# ST_LINK_V2-1.net
KiCad netlist of a schematic drawn in Altium Designer
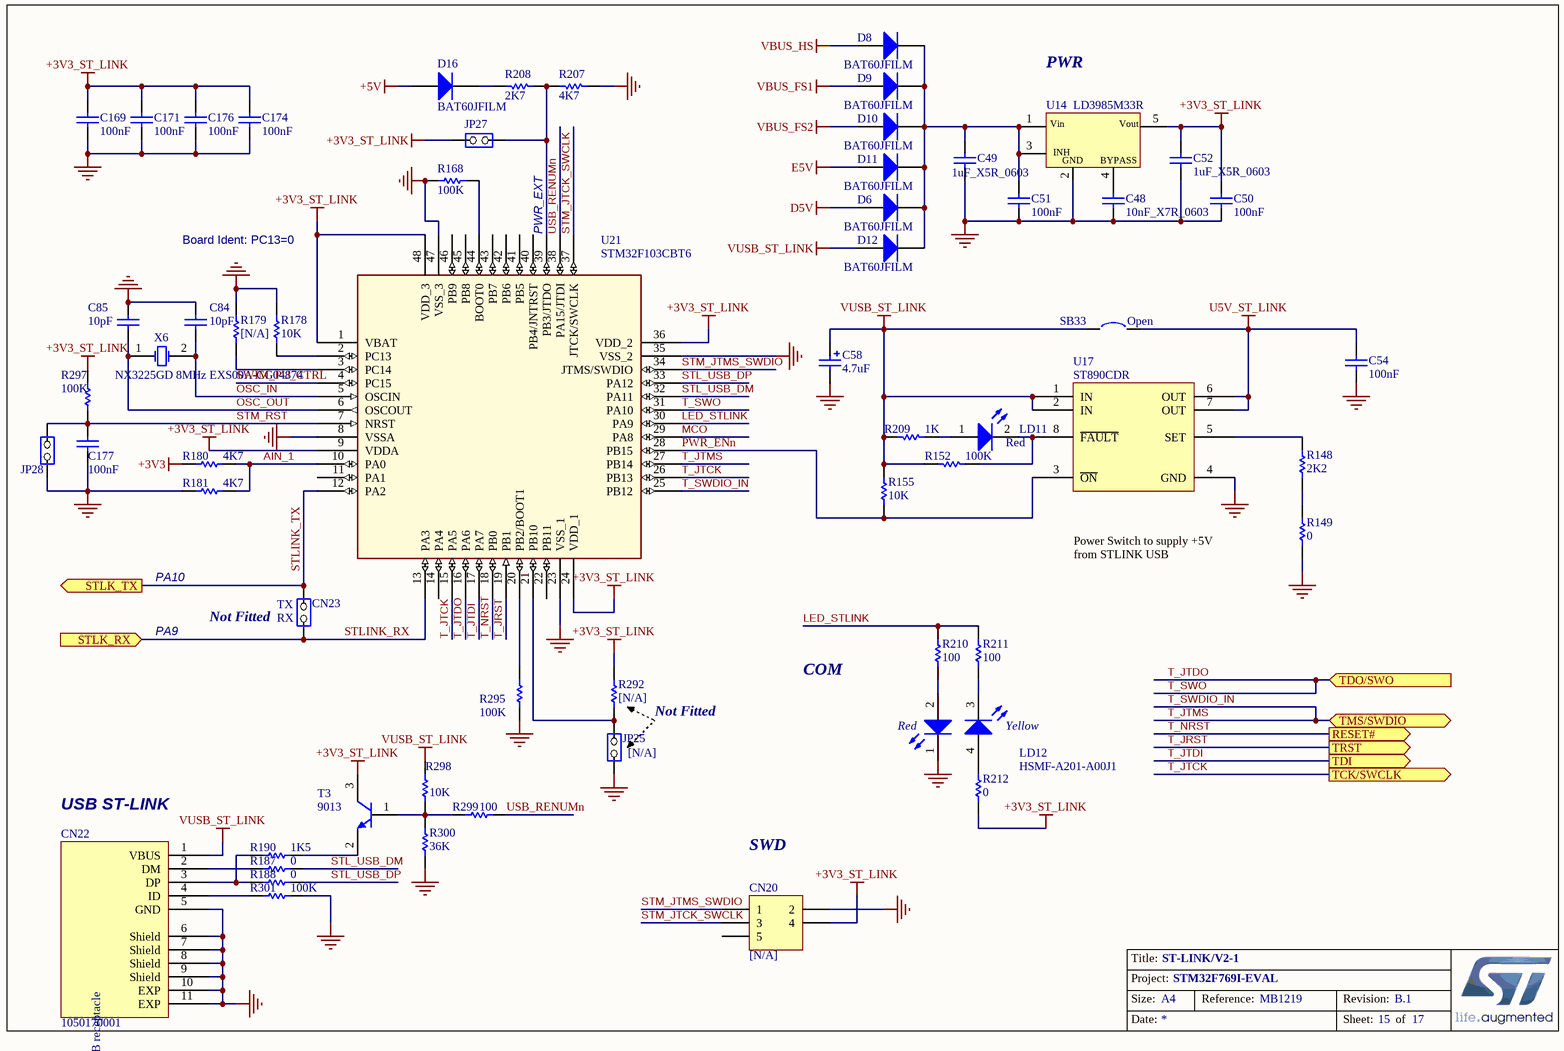
[diagram p0: ST_LINK_V2-1.SCHDOC]

(export (version "E")
  (design (tool "Eeschema 10.0.6"))
  (components
    (comp (ref "C48")
      (value "10nF_X7R_0603")
      (footprint "0603C")
      (description "0603  X7R 10NF")
      (fields (field (name "TOLERANCE") "10%"))
      (libsource (lib "MB963_1") (part "CAP SMD 0603  X7R 10000PF 50V 10%"))
    )
    (comp (ref "C49")
      (value "1uF_X5R_0603")
      (footprint "0603C")
      (description "0603  X5R 1µF")
      (fields (field (name "TOLERANCE") "10%"))
      (libsource (lib "MB963_1") (part "CAP SMD 0603  X5R 1µF 25V 10%"))
    )
    (comp (ref "C50")
      (value "100nF")
      (footprint "0603C")
      (description "Capacitor 0402 / 0603 / 0805")
      (libsource (lib "MCD_TOOLS") (part "Capacitor_ST"))
    )
    (comp (ref "C51")
      (value "100nF")
      (footprint "0603C")
      (description "Capacitor 0402 / 0603 / 0805")
      (libsource (lib "MCD_TOOLS") (part "Capacitor_ST"))
    )
    (comp (ref "C52")
      (value "1uF_X5R_0603")
      (footprint "0603C")
      (description "0603  X5R 1µF")
      (fields (field (name "TOLERANCE") "10%"))
      (libsource (lib "MB963_1") (part "CAP SMD 0603  X5R 1µF 25V 10%"))
    )
    (comp (ref "C54")
      (value "100nF")
      (footprint "0603C")
      (description "Capacitor 0402 / 0603 / 0805")
      (libsource (lib "MCD_TOOLS") (part "Capacitor_ST"))
    )
    (comp (ref "C58")
      (value "4.7uF")
      (footprint "TAN-A")
      (description "Polarized Capacitor (Radial)")
      (fields (field (name "PUBLISHER") "Altium Limited"))
      (libsource (lib "*") (part "Cap Pol1"))
    )
    (comp (ref "C84")
      (value "10pF")
      (footprint "0603C")
      (description "Capacitor 0402 / 0603 / 0805")
      (libsource (lib "MCD_TOOLS") (part "Capacitor_ST"))
    )
    (comp (ref "C85")
      (value "10pF")
      (footprint "0603C")
      (description "Capacitor 0402 / 0603 / 0805")
      (libsource (lib "MCD_TOOLS") (part "Capacitor_ST"))
    )
    (comp (ref "C169")
      (value "100nF")
      (footprint "0603C")
      (description "Capacitor 0402 / 0603 / 0805")
      (libsource (lib "MCD_TOOLS") (part "Capacitor_ST"))
    )
    (comp (ref "C171")
      (value "100nF")
      (footprint "0603C")
      (description "Capacitor 0402 / 0603 / 0805")
      (libsource (lib "MCD_TOOLS") (part "Capacitor_ST"))
    )
    (comp (ref "C174")
      (value "100nF")
      (footprint "0603C")
      (description "Capacitor 0402 / 0603 / 0805")
      (libsource (lib "MCD_TOOLS") (part "Capacitor_ST"))
    )
    (comp (ref "C176")
      (value "100nF")
      (footprint "0603C")
      (description "Capacitor 0402 / 0603 / 0805")
      (libsource (lib "MCD_TOOLS") (part "Capacitor_ST"))
    )
    (comp (ref "C177")
      (value "100nF")
      (footprint "0603C")
      (description "Capacitor 0402 / 0603 / 0805")
      (libsource (lib "MCD_TOOLS") (part "Capacitor_ST"))
    )
    (comp (ref "CN20")
      (value "[N/A]")
      (footprint "HDR_2X3-1_2R54-6")
      (description "Header, 3-Pin, Dual row")
      (fields (field (name "PUBLISHER") "Altium Limited"))
      (libsource (lib "Miscellaneous Connectors") (part "Header 3X2"))
    )
    (comp (ref "CN22")
      (value "1050170001")
      (footprint "Molex_1050170001")
      (libsource (lib "MB1219") (part "1050170001"))
    )
    (comp (ref "CN23") (value "~") (footprint "SIP2") (libsource (lib "MCD_TOOLS") (part "JP2")))
    (comp (ref "D6")
      (value "BAT60JFILM")
      (footprint "SOD-323")
      (libsource (lib "MCD_TOOLS") (part "BAT60JFILM"))
    )
    (comp (ref "D8")
      (value "BAT60JFILM")
      (footprint "SOD-323")
      (libsource (lib "MCD_TOOLS") (part "BAT60JFILM"))
    )
    (comp (ref "D9")
      (value "BAT60JFILM")
      (footprint "SOD-323")
      (libsource (lib "MCD_TOOLS") (part "BAT60JFILM"))
    )
    (comp (ref "D10")
      (value "BAT60JFILM")
      (footprint "SOD-323")
      (libsource (lib "MCD_TOOLS") (part "BAT60JFILM"))
    )
    (comp (ref "D11")
      (value "BAT60JFILM")
      (footprint "SOD-323")
      (libsource (lib "MCD_TOOLS") (part "BAT60JFILM"))
    )
    (comp (ref "D12")
      (value "BAT60JFILM")
      (footprint "SOD-323")
      (libsource (lib "MCD_TOOLS") (part "BAT60JFILM"))
    )
    (comp (ref "D16")
      (value "BAT60JFILM")
      (footprint "SOD-323")
      (description "Default Diode")
      (fields (field (name "PUBLISHER") "Altium Limited"))
      (libsource (lib "MB1144_1") (part "Diode"))
    )
    (comp (ref "JP25") (value "[N/A]") (footprint "SIP2") (libsource (lib "*") (part "JP2")))
    (comp (ref "JP27") (value "~") (footprint "SIP2") (libsource (lib "*") (part "JP2")))
    (comp (ref "JP28") (value "~") (footprint "SIP2") (libsource (lib "*") (part "JP2")))
    (comp (ref "LD11")
      (value "Red")
      (footprint "0603D")
      (description "Typical RED, GREEN, YELLOW, AMBER GaAs LED")
      (fields (field (name "PUBLISHER") "Altium Limited"))
      (libsource (lib "Miscellaneous Devices") (part "LED2"))
    )
    (comp (ref "LD12")
      (value "HSMF-A201-A00J1")
      (footprint "LED2_3528")
      (libsource (lib "MB819") (part "HSMF-A201-A00J1"))
    )
    (comp (ref "R148")
      (value "2K2")
      (footprint "0402R")
      (description "Resistor 0402 or 0603 or 0805")
      (libsource (lib "MCD_TOOLS") (part "Resistor_ST"))
    )
    (comp (ref "R149")
      (value "0")
      (footprint "0603R")
      (description "Resistor")
      (fields (field (name "PUBLISHER") "Altium Limited"))
      (libsource (lib "Miscellaneous Devices") (part "Res1"))
    )
    (comp (ref "R152")
      (value "100K")
      (footprint "0603R")
      (description "Resistor")
      (fields (field (name "PUBLISHER") "Altium Limited"))
      (libsource (lib "*") (part "Res1"))
    )
    (comp (ref "R155")
      (value "10K")
      (footprint "0402R")
      (description "Resistor 0402 or 0603 or 0805")
      (libsource (lib "MCD_TOOLS") (part "Resistor_ST"))
    )
    (comp (ref "R168")
      (value "100K")
      (footprint "0603R")
      (description "Resistor 0402 or 0603 or 0805")
      (libsource (lib "") (part "Res1_1"))
    )
    (comp (ref "R178")
      (value "10K")
      (footprint "0603R")
      (description "Resistor 0402 or 0603 or 0805")
      (libsource (lib "") (part "Res1_1"))
    )
    (comp (ref "R179")
      (value "[N/A]")
      (footprint "0603R")
      (description "Resistor 0402 or 0603 or 0805")
      (libsource (lib "") (part "Res1_1"))
    )
    (comp (ref "R180")
      (value "4K7")
      (footprint "0603R")
      (description "Resistor 0402 or 0603 or 0805")
      (libsource (lib "") (part "Res1_1"))
    )
    (comp (ref "R181")
      (value "4K7")
      (footprint "0603R")
      (description "Resistor 0402 or 0603 or 0805")
      (libsource (lib "") (part "Res1_1"))
    )
    (comp (ref "R187")
      (value "0")
      (footprint "0603R")
      (description "Resistor 0402 or 0603 or 0805")
      (libsource (lib "") (part "Res1_1"))
    )
    (comp (ref "R188")
      (value "0")
      (footprint "0603R")
      (description "Resistor 0402 or 0603 or 0805")
      (libsource (lib "") (part "Res1_1"))
    )
    (comp (ref "R190")
      (value "1K5")
      (footprint "0603R")
      (description "Resistor 0402 or 0603 or 0805")
      (libsource (lib "") (part "Res1_1"))
    )
    (comp (ref "R207")
      (value "4K7")
      (footprint "0603R")
      (description "Resistor")
      (fields (field (name "PUBLISHER") "Altium Limited"))
      (libsource (lib "") (part "Res1_2"))
    )
    (comp (ref "R208")
      (value "2K7")
      (footprint "0603R")
      (description "Resistor")
      (fields (field (name "PUBLISHER") "Altium Limited"))
      (libsource (lib "") (part "Res1_2"))
    )
    (comp (ref "R209")
      (value "1K")
      (footprint "0603R")
      (description "Resistor")
      (fields (field (name "PUBLISHER") "Altium Limited"))
      (libsource (lib "*") (part "Res1"))
    )
    (comp (ref "R210")
      (value "100")
      (footprint "0603R")
      (description "Resistor")
      (fields (field (name "PUBLISHER") "Altium Limited"))
      (libsource (lib "Miscellaneous Devices") (part "Res1"))
    )
    (comp (ref "R211")
      (value "100")
      (footprint "0603R")
      (description "Resistor")
      (fields (field (name "PUBLISHER") "Altium Limited"))
      (libsource (lib "Miscellaneous Devices") (part "Res1"))
    )
    (comp (ref "R212")
      (value "0")
      (footprint "0603R")
      (description "Resistor")
      (fields (field (name "PUBLISHER") "Altium Limited"))
      (libsource (lib "Miscellaneous Devices") (part "Res1"))
    )
    (comp (ref "R292")
      (value "[N/A]")
      (footprint "0603R")
      (description "Resistor")
      (fields (field (name "PUBLISHER") "Altium Limited"))
      (libsource (lib "Miscellaneous Devices") (part "Res1"))
    )
    (comp (ref "R295")
      (value "100K")
      (footprint "0603R")
      (description "Resistor 0402 or 0603 or 0805")
      (libsource (lib "") (part "Res1_1"))
    )
    (comp (ref "R297")
      (value "100K")
      (footprint "0603R")
      (description "Resistor 0402 or 0603 or 0805")
      (libsource (lib "") (part "Res1_1"))
    )
    (comp (ref "R298")
      (value "10K")
      (footprint "0603R")
      (description "Resistor")
      (fields (field (name "PUBLISHER") "Altium Limited"))
      (libsource (lib "Miscellaneous Devices") (part "Res1"))
    )
    (comp (ref "R299")
      (value "100")
      (footprint "0603R")
      (description "Resistor 0402 or 0603 or 0805")
      (libsource (lib "") (part "Res1_1"))
    )
    (comp (ref "R300")
      (value "36K")
      (footprint "0603R")
      (description "Resistor")
      (fields (field (name "PUBLISHER") "Altium Limited"))
      (libsource (lib "Miscellaneous Devices") (part "Res1"))
    )
    (comp (ref "R301")
      (value "100K")
      (footprint "0603R")
      (description "Resistor 0402 or 0603 or 0805")
      (libsource (lib "") (part "Res1_1"))
    )
    (comp (ref "SB33")
      (value "Open")
      (footprint "SB_0603")
      (description "Circuit Breaker")
      (fields (field (name "PUBLISHER") "Altium Limited"))
      (libsource (lib "MB1167") (part "Circuit Breaker"))
    )
    (comp (ref "T3")
      (value "9013")
      (footprint "SOT-23")
      (description "NPN Bipolar Transistor")
      (fields (field (name "PUBLISHER") "Altium Limited"))
      (libsource (lib "MB1167") (part "NPN"))
    )
    (comp (ref "U14")
      (value "LD3985M33R")
      (footprint "SOT23-5")
      (description "Ultra low drop-low noise BiCMOS voltage, regulators low ESR capacitors compatible")
      (libsource (lib "MCD_TOOLS") (part "LD3985M33R"))
    )
    (comp (ref "U17")
      (value "ST890CDR")
      (footprint "SOIC8_1R27_4R9X6")
      (libsource (lib "MB1219") (part "ST890CDR"))
    )
    (comp (ref "U21")
      (value "STM32F103CBT6")
      (footprint "LQFP48_0R5_9X9")
      (description "Medium-density performance line ARM-based 32-bit MCU with 64KB Flash")
      (libsource (lib "Nucleo_64") (part "STM32F103CBT6"))
    )
    (comp (ref "X6")
      (value "NX3225GD 8MHz EXS00A-CG04874")
      (footprint "XTAL_2SM_3R2X2R5_H1")
      (description "Crystal Oscillator")
      (fields (field (name "PUBLISHER") "Altium Limited"))
      (libsource (lib "MB963_1") (part "XTAL"))
    )
  )
  (nets
    (net (code "1") (name "+3V3") (class "Default")
      (node (ref "R180") (pin "1") (pinfunction "1_1") (pintype "passive"))
    )
    (net (code "2") (name "+3V3_ST_LINK") (class "Default")
      (node (ref "C169") (pin "2") (pinfunction "2_2") (pintype "passive"))
      (node (ref "C171") (pin "2") (pinfunction "2_2") (pintype "passive"))
      (node (ref "C174") (pin "2") (pinfunction "2_2") (pintype "passive"))
      (node (ref "C176") (pin "2") (pinfunction "2_2") (pintype "passive"))
      (node (ref "C50") (pin "2") (pinfunction "2_2") (pintype "passive"))
      (node (ref "C52") (pin "1") (pinfunction "1_1") (pintype "passive"))
      (node (ref "CN20") (pin "4") (pinfunction "4_4") (pintype "passive"))
      (node (ref "JP27") (pin "1") (pinfunction "COMMON_1") (pintype "passive"))
      (node (ref "R212") (pin "2") (pinfunction "2_2") (pintype "passive"))
      (node (ref "R292") (pin "1") (pinfunction "1_1") (pintype "passive"))
      (node (ref "R297") (pin "2") (pinfunction "2_2") (pintype "passive"))
      (node (ref "T3") (pin "3") (pinfunction "C_3") (pintype "passive"))
      (node (ref "U14") (pin "5") (pinfunction "Vout_5") (pintype "passive"))
      (node (ref "U21") (pin "1") (pinfunction "VBAT_1") (pintype "power_in"))
      (node (ref "U21") (pin "24") (pinfunction "VDD_1_24") (pintype "power_in"))
      (node (ref "U21") (pin "36") (pinfunction "VDD_2_36") (pintype "power_in"))
      (node (ref "U21") (pin "48") (pinfunction "VDD_3_48") (pintype "power_in"))
      (node (ref "U21") (pin "9") (pinfunction "VDDA_9") (pintype "power_in"))
    )
    (net (code "3") (name "+5V") (class "Default")
      (node (ref "D16") (pin "1") (pinfunction "A_1") (pintype "passive"))
    )
    (net (code "4") (name "/AIN_1") (class "Default")
      (node (ref "R180") (pin "2") (pinfunction "2_2") (pintype "passive"))
      (node (ref "R181") (pin "2") (pinfunction "2_2") (pintype "passive"))
      (node (ref "U21") (pin "10") (pinfunction "PA0_10") (pintype "bidirectional"))
    )
    (net (code "5") (name "/LED_STLINK") (class "Default")
      (node (ref "R210") (pin "1") (pinfunction "1_1") (pintype "passive"))
      (node (ref "R211") (pin "1") (pinfunction "1_1") (pintype "passive"))
      (node (ref "U21") (pin "30") (pinfunction "PA9_30") (pintype "bidirectional"))
    )
    (net (code "6") (name "/MCO") (class "Default")
      (node (ref "U21") (pin "29") (pinfunction "PA8_29") (pintype "bidirectional"))
    )
    (net (code "7") (name "/OSC_IN") (class "Default")
      (node (ref "C84") (pin "1") (pinfunction "1_1") (pintype "passive"))
      (node (ref "U21") (pin "5") (pinfunction "OSCIN_5") (pintype "input"))
      (node (ref "X6") (pin "2") (pinfunction "OSC2_2") (pintype "passive"))
    )
    (net (code "8") (name "/OSC_OUT") (class "Default")
      (node (ref "C85") (pin "1") (pinfunction "1_1") (pintype "passive"))
      (node (ref "U21") (pin "6") (pinfunction "OSCOUT_6") (pintype "output"))
      (node (ref "X6") (pin "1") (pinfunction "OSC1_1") (pintype "passive"))
    )
    (net (code "9") (name "/PWR_ENn") (class "Default")
      (node (ref "R155") (pin "2") (pinfunction "2_2") (pintype "passive"))
      (node (ref "U17") (pin "3") (pinfunction "~{ON}_3") (pintype "passive"))
      (node (ref "U21") (pin "28") (pinfunction "PB15_28") (pintype "bidirectional"))
    )
    (net (code "10") (name "/STLINK_RX") (class "Default")
      (node (ref "CN23") (pin "1") (pinfunction "COMMON_1") (pintype "passive"))
      (node (ref "U21") (pin "13") (pinfunction "PA3_13") (pintype "bidirectional"))
    )
    (net (code "11") (name "/STLINK_TX") (class "Default")
      (node (ref "CN23") (pin "2") (pinfunction "NO_2") (pintype "passive"))
      (node (ref "U21") (pin "12") (pinfunction "PA2_12") (pintype "bidirectional"))
    )
    (net (code "12") (name "/STL_USB_DM") (class "Default")
      (node (ref "R187") (pin "2") (pinfunction "2_2") (pintype "passive"))
      (node (ref "U21") (pin "32") (pinfunction "PA11_32") (pintype "bidirectional"))
    )
    (net (code "13") (name "/STL_USB_DP") (class "Default")
      (node (ref "R188") (pin "2") (pinfunction "2_2") (pintype "passive"))
      (node (ref "U21") (pin "33") (pinfunction "PA12_33") (pintype "bidirectional"))
    )
    (net (code "14") (name "/STM_JTCK_SWCLK") (class "Default")
      (node (ref "CN20") (pin "3") (pinfunction "3_3") (pintype "passive"))
      (node (ref "U21") (pin "37") (pinfunction "JTCK/SWCLK_37") (pintype "bidirectional"))
    )
    (net (code "15") (name "/STM_JTMS_SWDIO") (class "Default")
      (node (ref "CN20") (pin "1") (pinfunction "1_1") (pintype "passive"))
      (node (ref "U21") (pin "34") (pinfunction "JTMS/SWDIO_34") (pintype "bidirectional"))
    )
    (net (code "16") (name "/STM_RST") (class "Default")
      (node (ref "C177") (pin "2") (pinfunction "2_2") (pintype "passive"))
      (node (ref "JP28") (pin "2") (pinfunction "NO_2") (pintype "passive"))
      (node (ref "R297") (pin "1") (pinfunction "1_1") (pintype "passive"))
      (node (ref "U21") (pin "7") (pinfunction "NRST_7") (pintype "input"))
    )
    (net (code "17") (name "/SWIM_PU_CTRL") (class "Default")
      (node (ref "U21") (pin "4") (pinfunction "PC15_4") (pintype "bidirectional"))
    )
    (net (code "18") (name "/T_JRST") (class "Default")
      (node (ref "U21") (pin "19") (pinfunction "PB1_19") (pintype "input"))
    )
    (net (code "19") (name "/T_JTCK") (class "Default")
      (node (ref "U21") (pin "15") (pinfunction "PA5_15") (pintype "bidirectional"))
      (node (ref "U21") (pin "26") (pinfunction "PB13_26") (pintype "bidirectional"))
    )
    (net (code "20") (name "/T_JTDI") (class "Default")
      (node (ref "U21") (pin "17") (pinfunction "PA7_17") (pintype "bidirectional"))
    )
    (net (code "21") (name "/T_JTDO") (class "Default")
      (node (ref "U21") (pin "16") (pinfunction "PA6_16") (pintype "bidirectional"))
      (node (ref "U21") (pin "31") (pinfunction "PA10_31") (pintype "bidirectional"))
    )
    (net (code "22") (name "/T_JTMS") (class "Default")
      (node (ref "U21") (pin "25") (pinfunction "PB12_25") (pintype "bidirectional"))
      (node (ref "U21") (pin "27") (pinfunction "PB14_27") (pintype "bidirectional"))
    )
    (net (code "23") (name "/T_NRST") (class "Default")
      (node (ref "U21") (pin "18") (pinfunction "PB0_18") (pintype "bidirectional"))
    )
    (net (code "24") (name "/USB_RENUMn") (class "Default")
      (node (ref "R299") (pin "2") (pinfunction "2_2") (pintype "passive"))
      (node (ref "U21") (pin "38") (pinfunction "PA15/JTDI_38") (pintype "bidirectional"))
    )
    (net (code "25") (name "D5V") (class "Default")
      (node (ref "D6") (pin "1") (pinfunction "A_1") (pintype "passive"))
    )
    (net (code "26") (name "E5V") (class "Default")
      (node (ref "D11") (pin "1") (pinfunction "A_1") (pintype "passive"))
    )
    (net (code "27") (name "GND") (class "Default")
      (node (ref "C169") (pin "1") (pinfunction "1_1") (pintype "passive"))
      (node (ref "C171") (pin "1") (pinfunction "1_1") (pintype "passive"))
      (node (ref "C174") (pin "1") (pinfunction "1_1") (pintype "passive"))
      (node (ref "C176") (pin "1") (pinfunction "1_1") (pintype "passive"))
      (node (ref "C177") (pin "1") (pinfunction "1_1") (pintype "passive"))
      (node (ref "C48") (pin "1") (pinfunction "1_1") (pintype "passive"))
      (node (ref "C49") (pin "1") (pinfunction "1_1") (pintype "passive"))
      (node (ref "C50") (pin "1") (pinfunction "1_1") (pintype "passive"))
      (node (ref "C51") (pin "1") (pinfunction "1_1") (pintype "passive"))
      (node (ref "C52") (pin "2") (pinfunction "2_2") (pintype "passive"))
      (node (ref "C54") (pin "1") (pinfunction "1_1") (pintype "passive"))
      (node (ref "C58") (pin "2") (pinfunction "2_2") (pintype "passive"))
      (node (ref "C84") (pin "2") (pinfunction "2_2") (pintype "passive"))
      (node (ref "C85") (pin "2") (pinfunction "2_2") (pintype "passive"))
      (node (ref "CN20") (pin "2") (pinfunction "2_2") (pintype "passive"))
      (node (ref "CN22") (pin "10") (pinfunction "EXP_10") (pintype "passive"))
      (node (ref "CN22") (pin "11") (pinfunction "EXP_11") (pintype "passive"))
      (node (ref "CN22") (pin "5") (pinfunction "GND_5") (pintype "passive"))
      (node (ref "CN22") (pin "6") (pinfunction "Shield_6") (pintype "passive"))
      (node (ref "CN22") (pin "7") (pinfunction "Shield_7") (pintype "passive"))
      (node (ref "CN22") (pin "8") (pinfunction "Shield_8") (pintype "passive"))
      (node (ref "CN22") (pin "9") (pinfunction "Shield_9") (pintype "passive"))
      (node (ref "JP25") (pin "1") (pinfunction "COMMON_1") (pintype "passive"))
      (node (ref "JP28") (pin "1") (pinfunction "COMMON_1") (pintype "passive"))
      (node (ref "LD12") (pin "1") (pinfunction "RED_cathode_1") (pintype "passive"))
      (node (ref "R149") (pin "1") (pinfunction "1_1") (pintype "passive"))
      (node (ref "R168") (pin "1") (pinfunction "1_1") (pintype "passive"))
      (node (ref "R178") (pin "1") (pinfunction "1_1") (pintype "passive"))
      (node (ref "R179") (pin "1") (pinfunction "1_1") (pintype "passive"))
      (node (ref "R181") (pin "1") (pinfunction "1_1") (pintype "passive"))
      (node (ref "R207") (pin "2") (pinfunction "2_2") (pintype "passive"))
      (node (ref "R295") (pin "1") (pinfunction "1_1") (pintype "passive"))
      (node (ref "R300") (pin "1") (pinfunction "1_1") (pintype "passive"))
      (node (ref "R301") (pin "2") (pinfunction "2_2") (pintype "passive"))
      (node (ref "U14") (pin "2") (pinfunction "GND_2") (pintype "passive"))
      (node (ref "U17") (pin "4") (pinfunction "GND_4") (pintype "passive"))
      (node (ref "U21") (pin "23") (pinfunction "VSS_1_23") (pintype "power_in"))
      (node (ref "U21") (pin "35") (pinfunction "VSS_2_35") (pintype "power_in"))
      (node (ref "U21") (pin "47") (pinfunction "VSS_3_47") (pintype "power_in"))
      (node (ref "U21") (pin "8") (pinfunction "VSSA_8") (pintype "power_in"))
    )
    (net (code "28") (name "Net-(CN22-DM)") (class "Default")
      (node (ref "CN22") (pin "2") (pinfunction "DM_2") (pintype "passive"))
      (node (ref "R187") (pin "1") (pinfunction "1_1") (pintype "passive"))
    )
    (net (code "29") (name "Net-(CN22-DP)") (class "Default")
      (node (ref "CN22") (pin "3") (pinfunction "DP_3") (pintype "passive"))
      (node (ref "R188") (pin "1") (pinfunction "1_1") (pintype "passive"))
      (node (ref "R190") (pin "1") (pinfunction "1_1") (pintype "passive"))
    )
    (net (code "30") (name "Net-(CN22-ID)") (class "Default")
      (node (ref "CN22") (pin "4") (pinfunction "ID_4") (pintype "passive"))
      (node (ref "R301") (pin "1") (pinfunction "1_1") (pintype "passive"))
    )
    (net (code "31") (name "Net-(D10-K)") (class "Default")
      (node (ref "C49") (pin "2") (pinfunction "2_2") (pintype "passive"))
      (node (ref "C51") (pin "2") (pinfunction "2_2") (pintype "passive"))
      (node (ref "D10") (pin "2") (pinfunction "K_2") (pintype "passive"))
      (node (ref "D11") (pin "2") (pinfunction "K_2") (pintype "passive"))
      (node (ref "D12") (pin "2") (pinfunction "K_2") (pintype "passive"))
      (node (ref "D6") (pin "2") (pinfunction "K_2") (pintype "passive"))
      (node (ref "D8") (pin "2") (pinfunction "K_2") (pintype "passive"))
      (node (ref "D9") (pin "2") (pinfunction "K_2") (pintype "passive"))
      (node (ref "U14") (pin "1") (pinfunction "Vin_1") (pintype "passive"))
      (node (ref "U14") (pin "3") (pinfunction "CE_3") (pintype "passive"))
    )
    (net (code "32") (name "Net-(D16-K)") (class "Default")
      (node (ref "D16") (pin "2") (pinfunction "K_2") (pintype "passive"))
      (node (ref "R208") (pin "1") (pinfunction "1_1") (pintype "passive"))
    )
    (net (code "33") (name "Net-(JP25-NO)") (class "Default")
      (node (ref "JP25") (pin "2") (pinfunction "NO_2") (pintype "passive"))
      (node (ref "R292") (pin "2") (pinfunction "2_2") (pintype "passive"))
      (node (ref "U21") (pin "21") (pinfunction "PB10_21") (pintype "bidirectional"))
    )
    (net (code "34") (name "Net-(JP27-NO)") (class "Default")
      (node (ref "JP27") (pin "2") (pinfunction "NO_2") (pintype "passive"))
      (node (ref "R207") (pin "1") (pinfunction "1_1") (pintype "passive"))
      (node (ref "R208") (pin "2") (pinfunction "2_2") (pintype "passive"))
      (node (ref "U21") (pin "39") (pinfunction "PB3/JTDO_39") (pintype "bidirectional"))
    )
    (net (code "35") (name "Net-(LD11-A)") (class "Default")
      (node (ref "LD11") (pin "1") (pinfunction "A_1") (pintype "passive"))
      (node (ref "R209") (pin "2") (pinfunction "2_2") (pintype "passive"))
    )
    (net (code "36") (name "Net-(LD11-K)") (class "Default")
      (node (ref "LD11") (pin "2") (pinfunction "K_2") (pintype "passive"))
      (node (ref "R152") (pin "2") (pinfunction "2_2") (pintype "passive"))
      (node (ref "U17") (pin "8") (pinfunction "~{FAULT}_8") (pintype "passive"))
    )
    (net (code "37") (name "Net-(LD12-Red_anode)") (class "Default")
      (node (ref "LD12") (pin "2") (pinfunction "Red_anode_2") (pintype "passive"))
      (node (ref "R210") (pin "2") (pinfunction "2_2") (pintype "passive"))
    )
    (net (code "38") (name "Net-(LD12-YellowGreen_anode)") (class "Default")
      (node (ref "LD12") (pin "4") (pinfunction "YellowGreen_anode_4") (pintype "passive"))
      (node (ref "R212") (pin "1") (pinfunction "1_1") (pintype "passive"))
    )
    (net (code "39") (name "Net-(LD12-YellowGreen_cathode)") (class "Default")
      (node (ref "LD12") (pin "3") (pinfunction "YellowGreen_cathode_3") (pintype "passive"))
      (node (ref "R211") (pin "2") (pinfunction "2_2") (pintype "passive"))
    )
    (net (code "40") (name "Net-(R148-Pad1)") (class "Default")
      (node (ref "R148") (pin "1") (pinfunction "1_1") (pintype "passive"))
      (node (ref "R149") (pin "2") (pinfunction "2_2") (pintype "passive"))
    )
    (net (code "41") (name "Net-(T3-B)") (class "Default")
      (node (ref "R298") (pin "1") (pinfunction "1_1") (pintype "passive"))
      (node (ref "R299") (pin "1") (pinfunction "1_1") (pintype "passive"))
      (node (ref "R300") (pin "2") (pinfunction "2_2") (pintype "passive"))
      (node (ref "T3") (pin "1") (pinfunction "B_1") (pintype "passive"))
    )
    (net (code "42") (name "Net-(T3-E)") (class "Default")
      (node (ref "R190") (pin "2") (pinfunction "2_2") (pintype "passive"))
      (node (ref "T3") (pin "2") (pinfunction "E_2") (pintype "passive"))
    )
    (net (code "43") (name "Net-(U14-BYPASS)") (class "Default")
      (node (ref "C48") (pin "2") (pinfunction "2_2") (pintype "passive"))
      (node (ref "U14") (pin "4") (pinfunction "BYPASS_4") (pintype "passive"))
    )
    (net (code "44") (name "Net-(U17-SET)") (class "Default")
      (node (ref "R148") (pin "2") (pinfunction "2_2") (pintype "passive"))
      (node (ref "U17") (pin "5") (pinfunction "SET_5") (pintype "passive"))
    )
    (net (code "45") (name "Net-(U21-BOOT0)") (class "Default")
      (node (ref "R168") (pin "2") (pinfunction "2_2") (pintype "passive"))
      (node (ref "U21") (pin "44") (pinfunction "BOOT0_44") (pintype "bidirectional"))
    )
    (net (code "46") (name "Net-(U21-PB2{slash}BOOT1)") (class "Default")
      (node (ref "R295") (pin "2") (pinfunction "2_2") (pintype "passive"))
      (node (ref "U21") (pin "20") (pinfunction "PB2/BOOT1_20") (pintype "bidirectional"))
    )
    (net (code "47") (name "Net-(U21-PC13)") (class "Default")
      (node (ref "R178") (pin "2") (pinfunction "2_2") (pintype "passive"))
      (node (ref "U21") (pin "2") (pinfunction "PC13_2") (pintype "bidirectional"))
    )
    (net (code "48") (name "Net-(U21-PC14)") (class "Default")
      (node (ref "R179") (pin "2") (pinfunction "2_2") (pintype "passive"))
      (node (ref "U21") (pin "3") (pinfunction "PC14_3") (pintype "bidirectional"))
    )
    (net (code "49") (name "U5V_ST_LINK") (class "Default")
      (node (ref "C54") (pin "2") (pinfunction "2_2") (pintype "passive"))
      (node (ref "SB33") (pin "2") (pinfunction "2_2") (pintype "passive"))
      (node (ref "U17") (pin "6") (pinfunction "OUT_6") (pintype "passive"))
      (node (ref "U17") (pin "7") (pinfunction "OUT_7") (pintype "passive"))
    )
    (net (code "50") (name "VBUS_FS1") (class "Default")
      (node (ref "D9") (pin "1") (pinfunction "A_1") (pintype "passive"))
    )
    (net (code "51") (name "VBUS_FS2") (class "Default")
      (node (ref "D10") (pin "1") (pinfunction "A_1") (pintype "passive"))
    )
    (net (code "52") (name "VBUS_HS") (class "Default")
      (node (ref "D8") (pin "1") (pinfunction "A_1") (pintype "passive"))
    )
    (net (code "53") (name "VUSB_ST_LINK") (class "Default")
      (node (ref "C58") (pin "1") (pinfunction "1_1") (pintype "passive"))
      (node (ref "CN22") (pin "1") (pinfunction "VBUS_1") (pintype "passive"))
      (node (ref "D12") (pin "1") (pinfunction "A_1") (pintype "passive"))
      (node (ref "R152") (pin "1") (pinfunction "1_1") (pintype "passive"))
      (node (ref "R155") (pin "1") (pinfunction "1_1") (pintype "passive"))
      (node (ref "R209") (pin "1") (pinfunction "1_1") (pintype "passive"))
      (node (ref "R298") (pin "2") (pinfunction "2_2") (pintype "passive"))
      (node (ref "SB33") (pin "1") (pinfunction "1_1") (pintype "passive"))
      (node (ref "U17") (pin "1") (pinfunction "IN_1") (pintype "passive"))
      (node (ref "U17") (pin "2") (pinfunction "IN_2") (pintype "passive"))
    )
    (net (code "54") (name "unconnected-(CN20-Pad5)") (class "Default")
      (node (ref "CN20") (pin "5") (pinfunction "5_5") (pintype "passive"))
    )
    (net (code "55") (name "unconnected-(U21-PA1-Pad11)") (class "Default")
      (node (ref "U21") (pin "11") (pinfunction "PA1_11") (pintype "bidirectional"))
    )
    (net (code "56") (name "unconnected-(U21-PA4-Pad14)") (class "Default")
      (node (ref "U21") (pin "14") (pinfunction "PA4_14") (pintype "bidirectional"))
    )
    (net (code "57") (name "unconnected-(U21-PB4{slash}JNTRST-Pad40)") (class "Default")
      (node (ref "U21") (pin "40") (pinfunction "PB4/JNTRST_40") (pintype "bidirectional"))
    )
    (net (code "58") (name "unconnected-(U21-PB5-Pad41)") (class "Default")
      (node (ref "U21") (pin "41") (pinfunction "PB5_41") (pintype "bidirectional"))
    )
    (net (code "59") (name "unconnected-(U21-PB6-Pad42)") (class "Default")
      (node (ref "U21") (pin "42") (pinfunction "PB6_42") (pintype "bidirectional"))
    )
    (net (code "60") (name "unconnected-(U21-PB7-Pad43)") (class "Default")
      (node (ref "U21") (pin "43") (pinfunction "PB7_43") (pintype "bidirectional"))
    )
    (net (code "61") (name "unconnected-(U21-PB8-Pad45)") (class "Default")
      (node (ref "U21") (pin "45") (pinfunction "PB8_45") (pintype "bidirectional"))
    )
    (net (code "62") (name "unconnected-(U21-PB9-Pad46)") (class "Default")
      (node (ref "U21") (pin "46") (pinfunction "PB9_46") (pintype "bidirectional"))
    )
    (net (code "63") (name "unconnected-(U21-PB11-Pad22)") (class "Default")
      (node (ref "U21") (pin "22") (pinfunction "PB11_22") (pintype "bidirectional"))
    )
  )
)
